# rf.net
KiCad netlist of a schematic drawn in Altium Designer
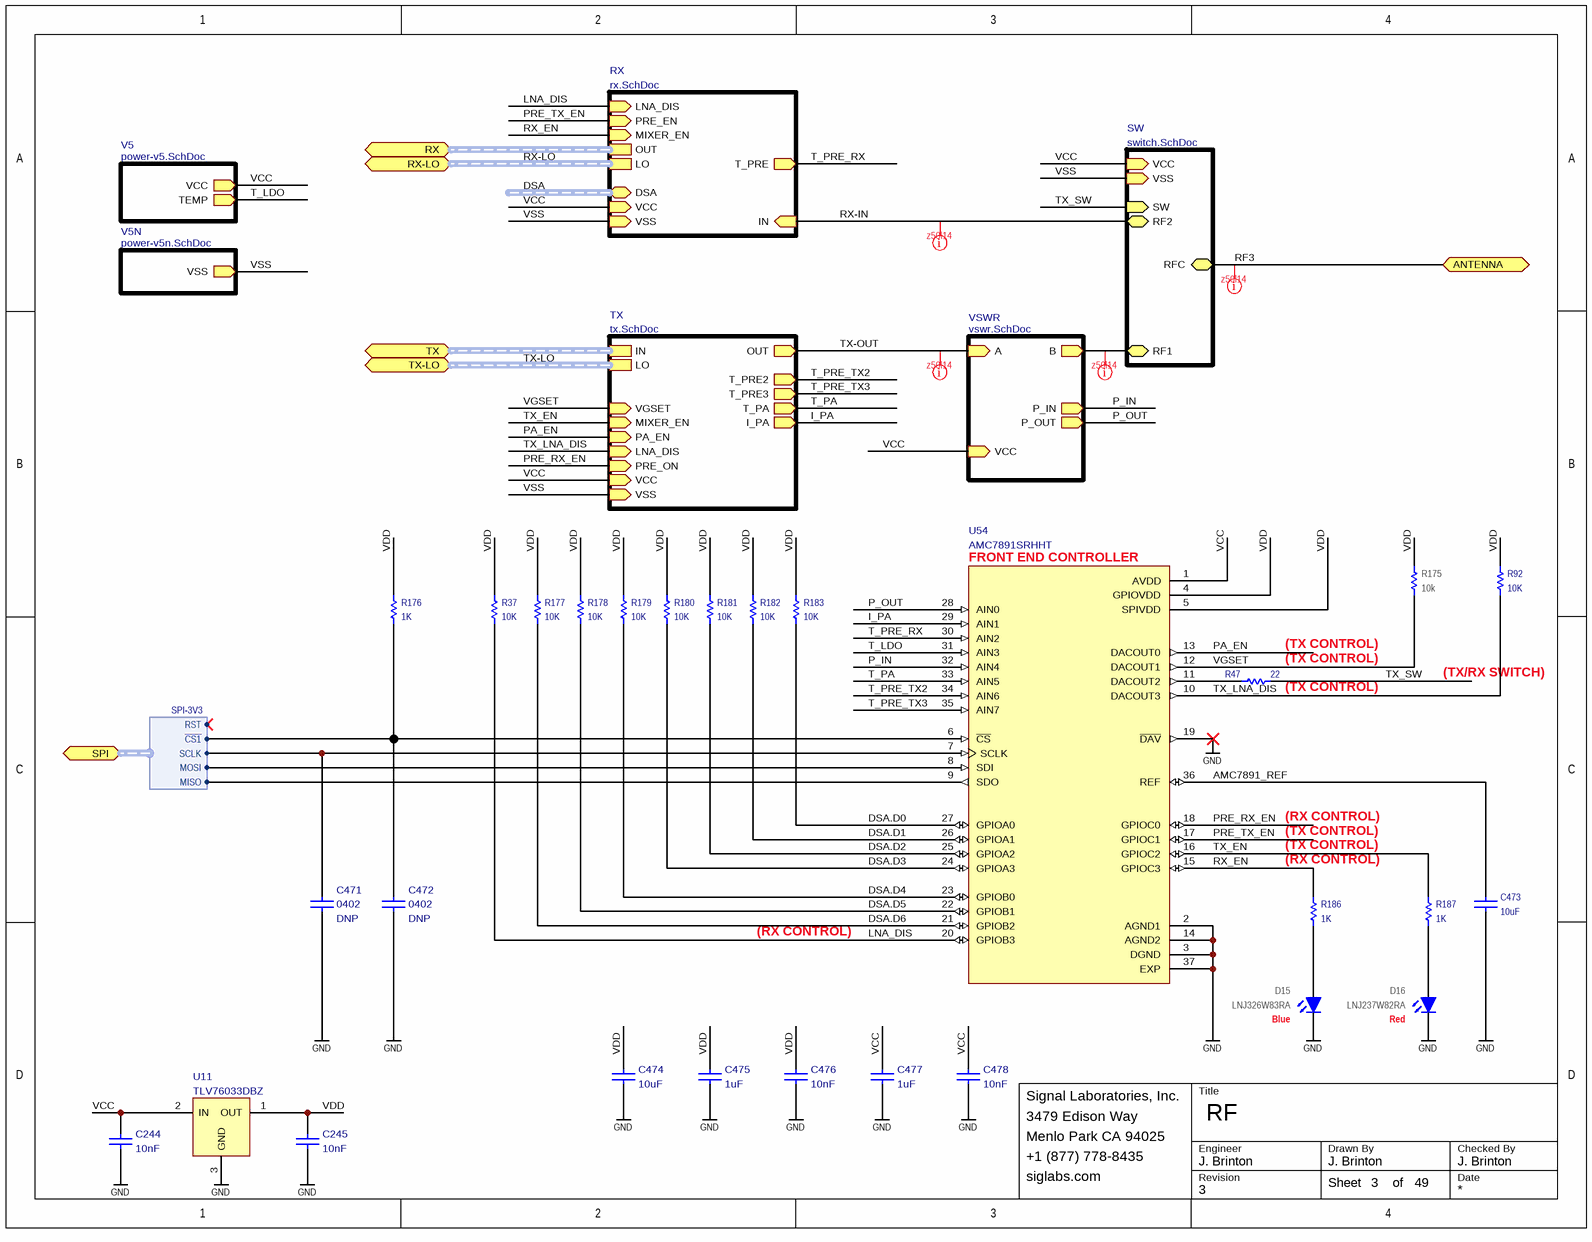
[diagram p0: rf.SchDoc]

(export (version "E")
  (design (tool "Eeschema 10.0.6"))
  (components
    (comp (ref "C244")
      (value "10nF")
      (footprint "CAPC100X50X55L25N")
      (description "Ceramic Capacitor 10nF ±10% 50V X7R 0402")
      (fields (field (name "MANUFACTURER") "Murata") (field (name "TOLERANCE") "±10%"))
      (libsource (lib "capacitors") (part "CAP"))
    )
    (comp (ref "C245")
      (value "10nF")
      (footprint "CAPC100X50X55L25N")
      (description "Ceramic Capacitor 10nF ±10% 50V X7R 0402")
      (fields (field (name "MANUFACTURER") "Murata") (field (name "TOLERANCE") "±10%"))
      (libsource (lib "capacitors") (part "CAP"))
    )
    (comp (ref "C471")
      (value "VJ0402A101KXA")
      (footprint "CAPC100X50X55L25N")
      (description "Ceramic Capacitor 100pF ±10% 50V C0G 0402")
      (fields
        (field (name "MANUFACTURER") "Vishay")
        (field (name "TOLERANCE") "±10%")
        (field (name "PACKAGE") "0402")
        (field (name "DO NOT PLACE") "DNP")
      )
      (libsource (lib "capacitors") (part "CAP"))
    )
    (comp (ref "C472")
      (value "VJ0402A101KXA")
      (footprint "CAPC100X50X55L25N")
      (description "Ceramic Capacitor 100pF ±10% 50V C0G 0402")
      (fields
        (field (name "MANUFACTURER") "Vishay")
        (field (name "TOLERANCE") "±10%")
        (field (name "PACKAGE") "0402")
        (field (name "DO NOT PLACE") "DNP")
      )
      (libsource (lib "capacitors") (part "CAP"))
    )
    (comp (ref "C473")
      (value "10uF")
      (footprint "CAPC160X80X90L20N")
      (description "Ceramic Capacitor 10uF ±20% 25V X5R 0603")
      (fields (field (name "MANUFACTURER") "Murata") (field (name "TOLERANCE") "±20%"))
      (libsource (lib "generic") (part "CAP"))
    )
    (comp (ref "C474")
      (value "10uF")
      (footprint "CAPC200X125X145L45N")
      (description "Ceramic Capacitor 10uF ±10% 16V X7R 0805")
      (fields (field (name "MANUFACTURER") "Samsung") (field (name "TOLERANCE") "±10%"))
      (libsource (lib "capacitors") (part "CAP"))
    )
    (comp (ref "C475")
      (value "1uF")
      (footprint "CAPC200X125X145L45N")
      (description "Ceramic Capacitor 1uF ±10% 25V X7R 0805")
      (fields (field (name "MANUFACTURER") "Taiyo Yuden") (field (name "TOLERANCE") "±10%"))
      (libsource (lib "capacitors") (part "CAP"))
    )
    (comp (ref "C476")
      (value "10nF")
      (footprint "CAPC100X50X55L25N")
      (description "Ceramic Capacitor 10nF ±10% 50V X7R 0402")
      (fields (field (name "MANUFACTURER") "Murata") (field (name "TOLERANCE") "±10%"))
      (libsource (lib "capacitors") (part "CAP"))
    )
    (comp (ref "C477")
      (value "1uF")
      (footprint "CAPC200X125X145L45N")
      (description "Ceramic Capacitor 1uF ±10% 25V X7R 0805")
      (fields (field (name "MANUFACTURER") "Taiyo Yuden") (field (name "TOLERANCE") "±10%"))
      (libsource (lib "capacitors") (part "CAP"))
    )
    (comp (ref "C478")
      (value "10nF")
      (footprint "CAPC100X50X55L25N")
      (description "Ceramic Capacitor 10nF ±10% 50V X7R 0402")
      (fields (field (name "MANUFACTURER") "Murata") (field (name "TOLERANCE") "±10%"))
      (libsource (lib "capacitors") (part "CAP"))
    )
    (comp (ref "D15")
      (value "LNJ326W83RA")
      (footprint "0603_LED")
      (description "LED, SMT 0603, Color Blue, 5mA, 2.9V")
      (fields (field (name "MANUFACTURER") "Panasonic"))
      (libsource (lib "generic") (part "LED0603GR"))
    )
    (comp (ref "D16")
      (value "LNJ237W82RA")
      (footprint "0603_LED")
      (description "LED, SMT 0603, Color Red, 10mA, 2.05V")
      (fields (field (name "MANUFACTURER") "Panasonic"))
      (libsource (lib "generic") (part "LED0603Y"))
    )
    (comp (ref "R37")
      (value "10K")
      (footprint "RESC1005X40N")
      (description "Thick Film Resistor 10k ±1% 0.1W 50V 0402")
      (fields (field (name "MANUFACTURER") "Panasonic") (field (name "TOLERANCE") "±1%"))
      (libsource (lib "Graviton") (part "RES 0402"))
    )
    (comp (ref "R47")
      (value "22")
      (footprint "RESC1005X40N")
      (description "Thick Film Resistor 22 ±1% 0402")
      (fields (field (name "MANUFACTURER") "Yageo") (field (name "TOLERANCE") "±1%"))
      (libsource (lib "Graviton") (part "RES 0402"))
    )
    (comp (ref "R92")
      (value "10K")
      (footprint "RESC1005X40N")
      (description "Thick Film Resistor 10k ±1% 0.1W 50V 0402")
      (fields (field (name "MANUFACTURER") "Panasonic") (field (name "TOLERANCE") "±1%"))
      (libsource (lib "Graviton") (part "RES 0402"))
    )
    (comp (ref "R175")
      (value "10k")
      (footprint "RESC1005X40N")
      (description "Thick Film Resistor 10k ±1% 0.1W 50V 0402")
      (fields (field (name "MANUFACTURER") "Panasonic") (field (name "TOLERANCE") "±1%"))
      (libsource (lib "generic") (part "RES"))
    )
    (comp (ref "R176")
      (value "1K")
      (footprint "RESC1005X40N")
      (description "Thick Film Resistor 1k ±1% 0402")
      (fields (field (name "MANUFACTURER") "Yageo") (field (name "TOLERANCE") "±1%"))
      (libsource (lib "Graviton") (part "RES 0402"))
    )
    (comp (ref "R177")
      (value "10K")
      (footprint "RESC1005X40N")
      (description "Thick Film Resistor 10k ±1% 0.1W 50V 0402")
      (fields (field (name "MANUFACTURER") "Panasonic") (field (name "TOLERANCE") "±1%"))
      (libsource (lib "Graviton") (part "RES 0402"))
    )
    (comp (ref "R178")
      (value "10K")
      (footprint "RESC1005X40N")
      (description "Thick Film Resistor 10k ±1% 0.1W 50V 0402")
      (fields (field (name "MANUFACTURER") "Panasonic") (field (name "TOLERANCE") "±1%"))
      (libsource (lib "Graviton") (part "RES 0402"))
    )
    (comp (ref "R179")
      (value "10K")
      (footprint "RESC1005X40N")
      (description "Thick Film Resistor 10k ±1% 0.1W 50V 0402")
      (fields (field (name "MANUFACTURER") "Panasonic") (field (name "TOLERANCE") "±1%"))
      (libsource (lib "Graviton") (part "RES 0402"))
    )
    (comp (ref "R180")
      (value "10K")
      (footprint "RESC1005X40N")
      (description "Thick Film Resistor 10k ±1% 0.1W 50V 0402")
      (fields (field (name "MANUFACTURER") "Panasonic") (field (name "TOLERANCE") "±1%"))
      (libsource (lib "Graviton") (part "RES 0402"))
    )
    (comp (ref "R181")
      (value "10K")
      (footprint "RESC1005X40N")
      (description "Thick Film Resistor 10k ±1% 0.1W 50V 0402")
      (fields (field (name "MANUFACTURER") "Panasonic") (field (name "TOLERANCE") "±1%"))
      (libsource (lib "Graviton") (part "RES 0402"))
    )
    (comp (ref "R182")
      (value "10K")
      (footprint "RESC1005X40N")
      (description "Thick Film Resistor 10k ±1% 0.1W 50V 0402")
      (fields (field (name "MANUFACTURER") "Panasonic") (field (name "TOLERANCE") "±1%"))
      (libsource (lib "Graviton") (part "RES 0402"))
    )
    (comp (ref "R183")
      (value "10K")
      (footprint "RESC1005X40N")
      (description "Thick Film Resistor 10k ±1% 0.1W 50V 0402")
      (fields (field (name "MANUFACTURER") "Panasonic") (field (name "TOLERANCE") "±1%"))
      (libsource (lib "Graviton") (part "RES 0402"))
    )
    (comp (ref "R186")
      (value "1K")
      (footprint "RESC1005X40N")
      (description "Thick Film Resistor 1k ±1% 0402")
      (fields (field (name "MANUFACTURER") "Yageo") (field (name "TOLERANCE") "±1%"))
      (libsource (lib "Graviton") (part "RES 0402"))
    )
    (comp (ref "R187")
      (value "1K")
      (footprint "RESC1005X40N")
      (description "Thick Film Resistor 1k ±1% 0402")
      (fields (field (name "MANUFACTURER") "Yageo") (field (name "TOLERANCE") "±1%"))
      (libsource (lib "Graviton") (part "RES 0402"))
    )
    (comp (ref "U11")
      (value "TLV76033DBZ")
      (footprint "generic:SOT23")
      (description "3.3V Fixed-Output LDO")
      (fields (field (name "MANUFACTURER") "Texas Instruments"))
      (libsource (lib "ti") (part "TLV76033DBZ"))
    )
    (comp (ref "U54")
      (value "AMC7891SRHHT")
      (footprint "QFN50P600X600X90-37N")
      (description "Analog Monitoring & Control IC")
      (fields (field (name "MANUFACTURER") "Texas Instruments"))
      (libsource (lib "ti") (part "AMC7891SRHHT"))
    )
  )
  (nets
    (net (code "7") (name "/AMC7891_REF") (class "Default")
      (node (ref "C473") (pin "2") (pinfunction "2_2") (pintype "passive"))
      (node (ref "U54") (pin "36") (pinfunction "REF_36") (pintype "bidirectional"))
    )
    (net (code "9") (name "/DSA.D0") (class "Default")
      (node (ref "R183") (pin "2") (pinfunction "2_2") (pintype "passive"))
      (node (ref "U54") (pin "27") (pinfunction "GPIOA0_27") (pintype "bidirectional"))
    )
    (net (code "10") (name "/DSA.D1") (class "Default")
      (node (ref "R182") (pin "2") (pinfunction "2_2") (pintype "passive"))
      (node (ref "U54") (pin "26") (pinfunction "GPIOA1_26") (pintype "bidirectional"))
    )
    (net (code "11") (name "/DSA.D2") (class "Default")
      (node (ref "R181") (pin "2") (pinfunction "2_2") (pintype "passive"))
      (node (ref "U54") (pin "25") (pinfunction "GPIOA2_25") (pintype "bidirectional"))
    )
    (net (code "12") (name "/DSA.D3") (class "Default")
      (node (ref "R180") (pin "2") (pinfunction "2_2") (pintype "passive"))
      (node (ref "U54") (pin "24") (pinfunction "GPIOA3_24") (pintype "bidirectional"))
    )
    (net (code "13") (name "/DSA.D4") (class "Default")
      (node (ref "R179") (pin "2") (pinfunction "2_2") (pintype "passive"))
      (node (ref "U54") (pin "23") (pinfunction "GPIOB0_23") (pintype "bidirectional"))
    )
    (net (code "14") (name "/DSA.D5") (class "Default")
      (node (ref "R178") (pin "2") (pinfunction "2_2") (pintype "passive"))
      (node (ref "U54") (pin "22") (pinfunction "GPIOB1_22") (pintype "bidirectional"))
    )
    (net (code "15") (name "/DSA.D6") (class "Default")
      (node (ref "R177") (pin "2") (pinfunction "2_2") (pintype "passive"))
      (node (ref "U54") (pin "21") (pinfunction "GPIOB2_21") (pintype "bidirectional"))
    )
    (net (code "16") (name "/I_PA") (class "Default")
      (node (ref "U54") (pin "29") (pinfunction "AIN1_29") (pintype "input"))
    )
    (net (code "17") (name "/LNA_DIS") (class "Default")
      (node (ref "R37") (pin "2") (pinfunction "2_2") (pintype "passive"))
      (node (ref "U54") (pin "20") (pinfunction "GPIOB3_20") (pintype "bidirectional"))
    )
    (net (code "18") (name "/MISO") (class "Default")
      (node (ref "U54") (pin "9") (pinfunction "SDO_9") (pintype "output"))
    )
    (net (code "19") (name "/MOSI") (class "Default")
      (node (ref "U54") (pin "8") (pinfunction "SDI_8") (pintype "input"))
    )
    (net (code "20") (name "/PA_EN") (class "Default")
      (node (ref "U54") (pin "13") (pinfunction "DACOUT0_13") (pintype "output"))
    )
    (net (code "21") (name "/PRE_RX_EN") (class "Default")
      (node (ref "U54") (pin "18") (pinfunction "GPIOC0_18") (pintype "bidirectional"))
    )
    (net (code "22") (name "/PRE_TX_EN") (class "Default")
      (node (ref "U54") (pin "17") (pinfunction "GPIOC1_17") (pintype "bidirectional"))
    )
    (net (code "23") (name "/P_IN") (class "Default")
      (node (ref "U54") (pin "32") (pinfunction "AIN4_32") (pintype "input"))
    )
    (net (code "24") (name "/P_OUT") (class "Default")
      (node (ref "U54") (pin "28") (pinfunction "AIN0_28") (pintype "input"))
    )
    (net (code "27") (name "/RX_EN") (class "Default")
      (node (ref "R186") (pin "2") (pinfunction "2_2") (pintype "passive"))
      (node (ref "U54") (pin "15") (pinfunction "GPIOC3_15") (pintype "bidirectional"))
    )
    (net (code "29") (name "/SCLK") (class "Default")
      (node (ref "C471") (pin "1") (pinfunction "1_1") (pintype "passive"))
      (node (ref "U54") (pin "7") (pinfunction "SCLK_7") (pintype "input"))
    )
    (net (code "31") (name "/TX_EN") (class "Default")
      (node (ref "R187") (pin "2") (pinfunction "2_2") (pintype "passive"))
      (node (ref "U54") (pin "16") (pinfunction "GPIOC2_16") (pintype "bidirectional"))
    )
    (net (code "32") (name "/TX_LNA_DIS") (class "Default")
      (node (ref "R92") (pin "2") (pinfunction "2_2") (pintype "passive"))
      (node (ref "U54") (pin "10") (pinfunction "DACOUT3_10") (pintype "output"))
    )
    (net (code "33") (name "/TX_SW") (class "Default")
      (node (ref "R47") (pin "2") (pinfunction "2_2") (pintype "passive"))
    )
    (net (code "35") (name "/T_LDO") (class "Default")
      (node (ref "U54") (pin "31") (pinfunction "AIN3_31") (pintype "input"))
    )
    (net (code "36") (name "/T_PA") (class "Default")
      (node (ref "U54") (pin "33") (pinfunction "AIN5_33") (pintype "input"))
    )
    (net (code "37") (name "/T_PRE_RX") (class "Default")
      (node (ref "U54") (pin "30") (pinfunction "AIN2_30") (pintype "input"))
    )
    (net (code "38") (name "/T_PRE_TX2") (class "Default")
      (node (ref "U54") (pin "34") (pinfunction "AIN6_34") (pintype "input"))
    )
    (net (code "39") (name "/T_PRE_TX3") (class "Default")
      (node (ref "U54") (pin "35") (pinfunction "AIN7_35") (pintype "input"))
    )
    (net (code "40") (name "/VCC") (class "Default")
      (node (ref "C244") (pin "1") (pinfunction "1_1") (pintype "passive"))
      (node (ref "C477") (pin "1") (pinfunction "1_1") (pintype "passive"))
      (node (ref "C478") (pin "1") (pinfunction "1_1") (pintype "passive"))
      (node (ref "U11") (pin "2") (pinfunction "IN_2") (pintype "passive"))
      (node (ref "U54") (pin "1") (pinfunction "AVDD_1") (pintype "power_in"))
    )
    (net (code "41") (name "/VDD") (class "Default")
      (node (ref "C245") (pin "1") (pinfunction "1_1") (pintype "passive"))
      (node (ref "C474") (pin "1") (pinfunction "1_1") (pintype "passive"))
      (node (ref "C475") (pin "1") (pinfunction "1_1") (pintype "passive"))
      (node (ref "C476") (pin "1") (pinfunction "1_1") (pintype "passive"))
      (node (ref "R175") (pin "1") (pinfunction "1_1") (pintype "passive"))
      (node (ref "R176") (pin "2") (pinfunction "2_2") (pintype "passive"))
      (node (ref "R177") (pin "1") (pinfunction "1_1") (pintype "passive"))
      (node (ref "R178") (pin "1") (pinfunction "1_1") (pintype "passive"))
      (node (ref "R179") (pin "1") (pinfunction "1_1") (pintype "passive"))
      (node (ref "R180") (pin "1") (pinfunction "1_1") (pintype "passive"))
      (node (ref "R181") (pin "1") (pinfunction "1_1") (pintype "passive"))
      (node (ref "R182") (pin "1") (pinfunction "1_1") (pintype "passive"))
      (node (ref "R183") (pin "1") (pinfunction "1_1") (pintype "passive"))
      (node (ref "R37") (pin "1") (pinfunction "1_1") (pintype "passive"))
      (node (ref "R92") (pin "1") (pinfunction "1_1") (pintype "passive"))
      (node (ref "U11") (pin "1") (pinfunction "OUT_1") (pintype "passive"))
      (node (ref "U54") (pin "4") (pinfunction "GPIOVDD_4") (pintype "power_in"))
      (node (ref "U54") (pin "5") (pinfunction "SPIVDD_5") (pintype "power_in"))
    )
    (net (code "42") (name "/VGSET") (class "Default")
      (node (ref "R175") (pin "2") (pinfunction "2_2") (pintype "passive"))
      (node (ref "U54") (pin "12") (pinfunction "DACOUT1_12") (pintype "output"))
    )
    (net (code "48") (name "/~{CS1}") (class "Default")
      (node (ref "C472") (pin "1") (pinfunction "1_1") (pintype "passive"))
      (node (ref "R176") (pin "1") (pinfunction "1_1") (pintype "passive"))
      (node (ref "U54") (pin "6") (pinfunction "~{CS}_6") (pintype "input"))
    )
    (net (code "49") (name "GND") (class "Default")
      (node (ref "C244") (pin "2") (pinfunction "2_2") (pintype "passive"))
      (node (ref "C245") (pin "2") (pinfunction "2_2") (pintype "passive"))
      (node (ref "C471") (pin "2") (pinfunction "2_2") (pintype "passive"))
      (node (ref "C472") (pin "2") (pinfunction "2_2") (pintype "passive"))
      (node (ref "C473") (pin "1") (pinfunction "1_1") (pintype "passive"))
      (node (ref "C474") (pin "2") (pinfunction "2_2") (pintype "passive"))
      (node (ref "C475") (pin "2") (pinfunction "2_2") (pintype "passive"))
      (node (ref "C476") (pin "2") (pinfunction "2_2") (pintype "passive"))
      (node (ref "C477") (pin "2") (pinfunction "2_2") (pintype "passive"))
      (node (ref "C478") (pin "2") (pinfunction "2_2") (pintype "passive"))
      (node (ref "D15") (pin "2") (pinfunction "K_2") (pintype "passive"))
      (node (ref "D16") (pin "2") (pinfunction "K_2") (pintype "passive"))
      (node (ref "U11") (pin "3") (pinfunction "GND_3") (pintype "passive"))
      (node (ref "U54") (pin "14") (pinfunction "AGND2_14") (pintype "power_in"))
      (node (ref "U54") (pin "19") (pinfunction "~{DAV}_19") (pintype "output"))
      (node (ref "U54") (pin "2") (pinfunction "AGND1_2") (pintype "power_in"))
      (node (ref "U54") (pin "3") (pinfunction "DGND_3") (pintype "power_in"))
      (node (ref "U54") (pin "37") (pinfunction "EXP_37") (pintype "power_in"))
    )
    (net (code "50") (name "Net-(D15-A)") (class "Default")
      (node (ref "D15") (pin "1") (pinfunction "A_1") (pintype "passive"))
      (node (ref "R186") (pin "1") (pinfunction "1_1") (pintype "passive"))
    )
    (net (code "51") (name "Net-(D16-A)") (class "Default")
      (node (ref "D16") (pin "1") (pinfunction "A_1") (pintype "passive"))
      (node (ref "R187") (pin "1") (pinfunction "1_1") (pintype "passive"))
    )
    (net (code "52") (name "Net-(U54-DACOUT2)") (class "Default")
      (node (ref "R47") (pin "1") (pinfunction "1_1") (pintype "passive"))
      (node (ref "U54") (pin "11") (pinfunction "DACOUT2_11") (pintype "output"))
    )
  )
)
